# Radio_XBP9X_DMRS_001.net
KiCad netlist of a schematic drawn in Altium Designer
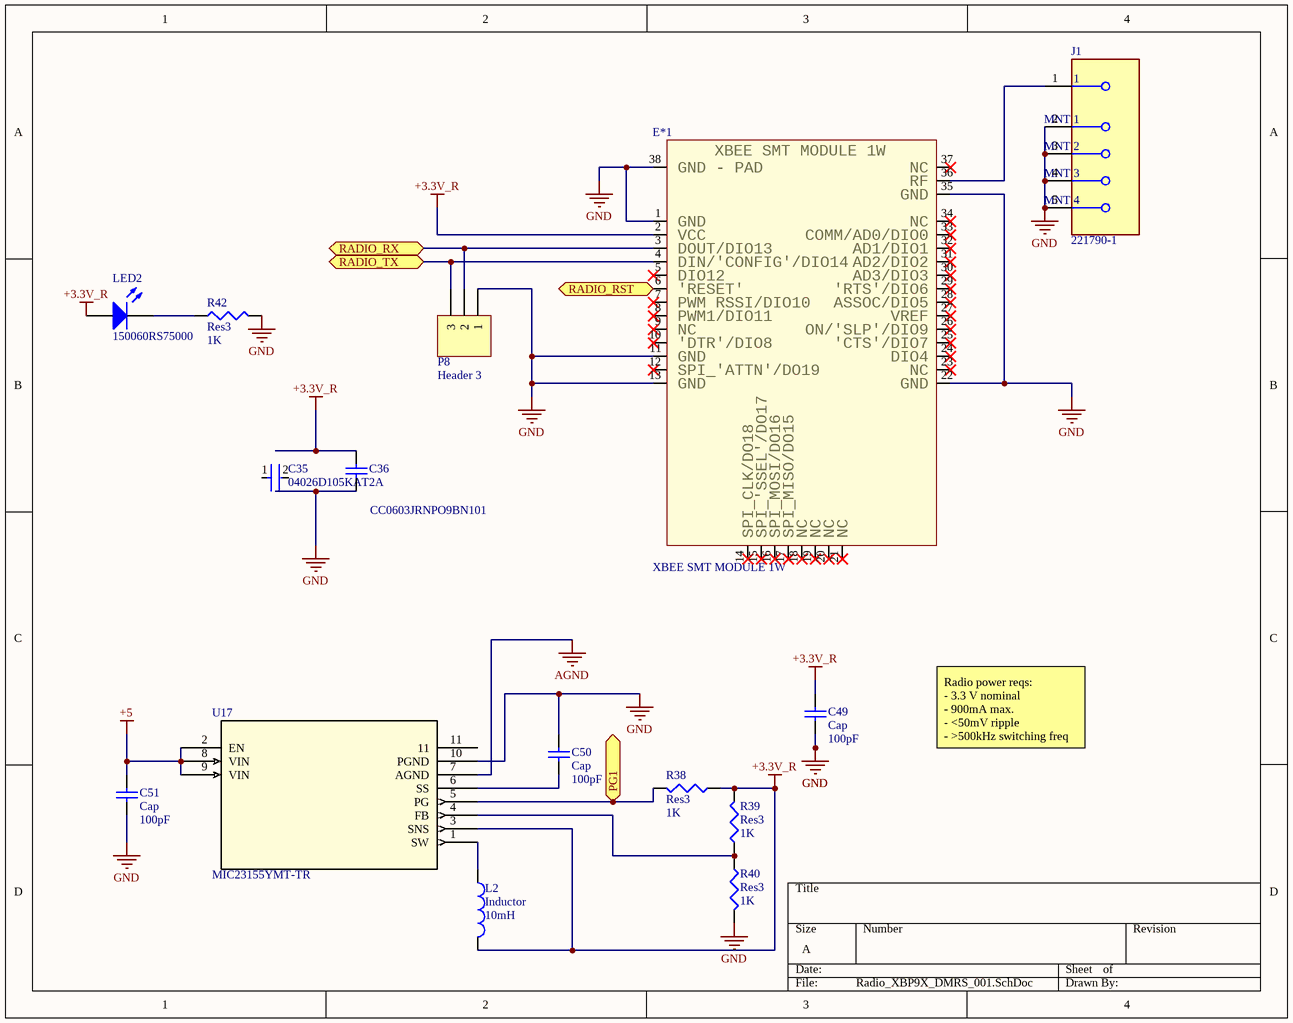
[diagram p0: Radio_XBP9X_DMRS_001.SchDoc]

(export (version "E")
  (design (tool "Eeschema 10.0.6"))
  (components
    (comp (ref "C35")
      (value "04026D105KAT2A")
      (footprint "FP-0402-L_1_0_1-W_0_5_0_1-MFG")
      (description "General Purpose Ceramic Capacitor, 0402, 1uF, 10%, X5R, 15%, 6.3V")
      (fields (field (name "TOLERANCE") "10%") (field (name "VOLTAGE") "6.3V"))
      (libsource (lib "Altium Content Vault") (part "b4654b650e69147ec39a6b967a45e02"))
    )
    (comp (ref "C36")
      (value "CC0603JRNPO9BN101")
      (footprint "CAPC1608X90X40ML10T20")
      (description "Chip Capacitor, 100 pF, +/- 5%, 50 V, -55 to 125 degC, 0603 (1608 Metric), RoHS, Tape and Reel")
      (fields (field (name "TOLERANCE") "5%") (field (name "VOLTAGE") "50V"))
      (libsource (lib "Altium Content Vault") (part "CAP-NP-2"))
    )
    (comp (ref "C49")
      (value "Cap")
      (footprint "RAD-0.3")
      (description "Capacitor")
      (fields (field (name "ALTIUM_VALUE") "100pF") (field (name "PUBLISHER") "Altium Limited"))
      (libsource (lib "Miscellaneous Devices") (part "Cap"))
    )
    (comp (ref "C50")
      (value "Cap")
      (footprint "RAD-0.3")
      (description "Capacitor")
      (fields (field (name "ALTIUM_VALUE") "100pF") (field (name "PUBLISHER") "Altium Limited"))
      (libsource (lib "Miscellaneous Devices") (part "Cap"))
    )
    (comp (ref "C51")
      (value "Cap")
      (footprint "RAD-0.3")
      (description "Capacitor")
      (fields (field (name "ALTIUM_VALUE") "100pF") (field (name "PUBLISHER") "Altium Limited"))
      (libsource (lib "Miscellaneous Devices") (part "Cap"))
    )
    (comp (ref "E*1")
      (value "XBEE SMT MODULE 1W")
      (libsource (lib "Xbee3_1W_Customer_Sch_Symbol") (part "XBEE SMT MODULE 1W"))
    )
    (comp (ref "J1")
      (value "221790-1")
      (footprint "FP-221790-1-MFG")
      (description "CONN SMA JACK R/A 50 OHM PCB")
      (fields
        (field (name "OCTOPART") "https://octopart.com/2217901-te+connectivity+%2F+amp-3339836")
        (field (name "MANUFACTURER") "TE Connectivity / AMP")
      )
      (libsource (lib "Altium Content Vault") (part "c65b8a639cdaef1819ea20b5466f8fa"))
    )
    (comp (ref "L2")
      (value "Inductor")
      (footprint "0402-A")
      (fields (field (name "ALTIUM_VALUE") "10mH") (field (name "PUBLISHER") "Altium Limited"))
      (libsource (lib "Miscellaneous Devices") (part "Inductor"))
    )
    (comp (ref "LED2")
      (value "150060RS75000")
      (footprint "0603_A")
      (description "SMD mono-color Chip LED, WL-SMCW, Red")
      (fields (field (name "MANUFACTURER") "Wuerth Elektronik"))
      (libsource (lib "Altium Content Vault") (part "WE-LED_K1A2-2"))
    )
    (comp (ref "P8")
      (value "Header 3")
      (footprint "HDR1X3")
      (description "Header, 3-Pin")
      (fields (field (name "PUBLISHER") "Altium Limited"))
      (libsource (lib "Miscellaneous Connectors") (part "Header 3"))
    )
    (comp (ref "R38")
      (value "Res3")
      (footprint "J1-0603")
      (description "Resistor")
      (fields (field (name "ALTIUM_VALUE") "1K") (field (name "PUBLISHER") "Altium Limited"))
      (libsource (lib "Miscellaneous Devices") (part "Res3"))
    )
    (comp (ref "R39")
      (value "Res3")
      (footprint "J1-0603")
      (description "Resistor")
      (fields (field (name "ALTIUM_VALUE") "1K") (field (name "PUBLISHER") "Altium Limited"))
      (libsource (lib "Miscellaneous Devices") (part "Res3"))
    )
    (comp (ref "R40")
      (value "Res3")
      (footprint "J1-0603")
      (description "Resistor")
      (fields (field (name "ALTIUM_VALUE") "1K") (field (name "PUBLISHER") "Altium Limited"))
      (libsource (lib "Miscellaneous Devices") (part "Res3"))
    )
    (comp (ref "R42")
      (value "Res3")
      (footprint "J1-0603")
      (description "Resistor")
      (fields (field (name "ALTIUM_VALUE") "1K") (field (name "PUBLISHER") "Altium Limited"))
      (libsource (lib "Miscellaneous Devices") (part "Res3"))
    )
    (comp (ref "U17")
      (value "MIC23155YMT-TR")
      (footprint "DFN-10_MCH")
      (description "No Description Available")
      (fields (field (name "COPYRIGHT") "Copyright (C) 2018 Accelerated Designs. All rights reserved"))
      (libsource (lib "MIC23155") (part "MIC23155YMT-TR"))
    )
  )
  (nets
    (net (code "1") (name "+3.3V_R") (class "Default")
      (node (ref "C36") (pin "2") (pinfunction "2_2") (pintype "passive"))
      (node (ref "C49") (pin "2") (pinfunction "2_2") (pintype "passive"))
      (node (ref "E*1") (pin "2") (pintype "passive"))
      (node (ref "L2") (pin "2") (pinfunction "2_2") (pintype "passive"))
      (node (ref "LED2") (pin "2") (pinfunction "A_2") (pintype "passive"))
      (node (ref "R38") (pin "1") (pinfunction "1_1") (pintype "passive"))
      (node (ref "R39") (pin "2") (pinfunction "2_2") (pintype "passive"))
      (node (ref "U17") (pin "3") (pinfunction "SNS_3") (pintype "output"))
    )
    (net (code "2") (name "+5") (class "Default")
      (node (ref "C51") (pin "2") (pinfunction "2_2") (pintype "passive"))
      (node (ref "U17") (pin "2") (pinfunction "EN_2") (pintype "passive"))
      (node (ref "U17") (pin "8") (pinfunction "VIN_8") (pintype "input"))
      (node (ref "U17") (pin "9") (pinfunction "VIN_9") (pintype "input"))
    )
    (net (code "3") (name "/PG1") (class "Default")
      (node (ref "R38") (pin "2") (pinfunction "2_2") (pintype "passive"))
      (node (ref "U17") (pin "5") (pinfunction "PG_5") (pintype "output"))
    )
    (net (code "4") (name "/RADIO_RST") (class "Default") (node (ref "E*1") (pin "6") (pintype "passive")))
    (net (code "5") (name "/RADIO_RX") (class "Default")
      (node (ref "E*1") (pin "3") (pintype "passive"))
      (node (ref "P8") (pin "2") (pinfunction "2_2") (pintype "passive"))
    )
    (net (code "6") (name "/RADIO_TX") (class "Default")
      (node (ref "E*1") (pin "4") (pintype "passive"))
      (node (ref "P8") (pin "3") (pinfunction "3_3") (pintype "passive"))
    )
    (net (code "7") (name "AGND") (class "Default")
      (node (ref "U17") (pin "7") (pinfunction "AGND_7") (pintype "power_in"))
    )
    (net (code "8") (name "GND") (class "Default")
      (node (ref "C36") (pin "1") (pinfunction "1_1") (pintype "passive"))
      (node (ref "C49") (pin "1") (pinfunction "1_1") (pintype "passive"))
      (node (ref "C50") (pin "2") (pinfunction "2_2") (pintype "passive"))
      (node (ref "C51") (pin "1") (pinfunction "1_1") (pintype "passive"))
      (node (ref "E*1") (pin "1") (pintype "passive"))
      (node (ref "E*1") (pin "11") (pintype "passive"))
      (node (ref "E*1") (pin "13") (pintype "passive"))
      (node (ref "E*1") (pin "22") (pintype "passive"))
      (node (ref "E*1") (pin "35") (pintype "passive"))
      (node (ref "E*1") (pin "38") (pintype "passive"))
      (node (ref "J1") (pin "2") (pinfunction "MNT_1_2") (pintype "passive"))
      (node (ref "J1") (pin "3") (pinfunction "MNT_2_3") (pintype "passive"))
      (node (ref "J1") (pin "4") (pinfunction "MNT_3_4") (pintype "passive"))
      (node (ref "J1") (pin "5") (pinfunction "MNT_4_5") (pintype "passive"))
      (node (ref "P8") (pin "1") (pinfunction "1_1") (pintype "passive"))
      (node (ref "R40") (pin "2") (pinfunction "2_2") (pintype "passive"))
      (node (ref "R42") (pin "2") (pinfunction "2_2") (pintype "passive"))
      (node (ref "U17") (pin "10") (pinfunction "PGND_10") (pintype "power_in"))
    )
    (net (code "9") (name "Net-(E*1-Pad36)") (class "Default")
      (node (ref "E*1") (pin "36") (pintype "passive"))
      (node (ref "J1") (pin "1") (pinfunction "1_1") (pintype "passive"))
    )
    (net (code "10") (name "Net-(LED2-K)") (class "Default")
      (node (ref "LED2") (pin "1") (pinfunction "K_1") (pintype "passive"))
      (node (ref "R42") (pin "1") (pinfunction "1_1") (pintype "passive"))
    )
    (net (code "11") (name "Net-(U17-FB)") (class "Default")
      (node (ref "R39") (pin "1") (pinfunction "1_1") (pintype "passive"))
      (node (ref "R40") (pin "1") (pinfunction "1_1") (pintype "passive"))
      (node (ref "U17") (pin "4") (pinfunction "FB_4") (pintype "output"))
    )
    (net (code "12") (name "Net-(U17-SS)") (class "Default")
      (node (ref "C50") (pin "1") (pinfunction "1_1") (pintype "passive"))
      (node (ref "U17") (pin "6") (pinfunction "SS_6") (pintype "passive"))
    )
    (net (code "13") (name "Net-(U17-SW)") (class "Default")
      (node (ref "L2") (pin "1") (pinfunction "1_1") (pintype "passive"))
      (node (ref "U17") (pin "1") (pinfunction "SW_1") (pintype "output"))
    )
    (net (code "14") (name "unconnected-(C35-Pad1)") (class "Default")
      (node (ref "C35") (pin "1") (pinfunction "1_1") (pintype "passive"))
    )
    (net (code "15") (name "unconnected-(C35-Pad2)") (class "Default")
      (node (ref "C35") (pin "2") (pinfunction "2_2") (pintype "passive"))
    )
    (net (code "16") (name "unconnected-(E*1-Pad5)") (class "Default")
      (node (ref "E*1") (pin "5") (pintype "passive+no_connect"))
    )
    (net (code "17") (name "unconnected-(E*1-Pad7)") (class "Default")
      (node (ref "E*1") (pin "7") (pintype "passive+no_connect"))
    )
    (net (code "18") (name "unconnected-(E*1-Pad8)") (class "Default")
      (node (ref "E*1") (pin "8") (pintype "passive+no_connect"))
    )
    (net (code "19") (name "unconnected-(E*1-Pad9)") (class "Default")
      (node (ref "E*1") (pin "9") (pintype "passive+no_connect"))
    )
    (net (code "20") (name "unconnected-(E*1-Pad10)") (class "Default")
      (node (ref "E*1") (pin "10") (pintype "passive+no_connect"))
    )
    (net (code "21") (name "unconnected-(E*1-Pad12)") (class "Default")
      (node (ref "E*1") (pin "12") (pintype "passive+no_connect"))
    )
    (net (code "22") (name "unconnected-(E*1-Pad14)") (class "Default")
      (node (ref "E*1") (pin "14") (pintype "passive+no_connect"))
    )
    (net (code "23") (name "unconnected-(E*1-Pad15)") (class "Default")
      (node (ref "E*1") (pin "15") (pintype "passive+no_connect"))
    )
    (net (code "24") (name "unconnected-(E*1-Pad16)") (class "Default")
      (node (ref "E*1") (pin "16") (pintype "passive+no_connect"))
    )
    (net (code "25") (name "unconnected-(E*1-Pad17)") (class "Default")
      (node (ref "E*1") (pin "17") (pintype "passive+no_connect"))
    )
    (net (code "26") (name "unconnected-(E*1-Pad18)") (class "Default")
      (node (ref "E*1") (pin "18") (pintype "passive+no_connect"))
    )
    (net (code "27") (name "unconnected-(E*1-Pad19)") (class "Default")
      (node (ref "E*1") (pin "19") (pintype "passive+no_connect"))
    )
    (net (code "28") (name "unconnected-(E*1-Pad20)") (class "Default")
      (node (ref "E*1") (pin "20") (pintype "passive+no_connect"))
    )
    (net (code "29") (name "unconnected-(E*1-Pad21)") (class "Default")
      (node (ref "E*1") (pin "21") (pintype "passive+no_connect"))
    )
    (net (code "30") (name "unconnected-(E*1-Pad23)") (class "Default")
      (node (ref "E*1") (pin "23") (pintype "passive+no_connect"))
    )
    (net (code "31") (name "unconnected-(E*1-Pad24)") (class "Default")
      (node (ref "E*1") (pin "24") (pintype "passive+no_connect"))
    )
    (net (code "32") (name "unconnected-(E*1-Pad25)") (class "Default")
      (node (ref "E*1") (pin "25") (pintype "passive+no_connect"))
    )
    (net (code "33") (name "unconnected-(E*1-Pad26)") (class "Default")
      (node (ref "E*1") (pin "26") (pintype "passive+no_connect"))
    )
    (net (code "34") (name "unconnected-(E*1-Pad27)") (class "Default")
      (node (ref "E*1") (pin "27") (pintype "passive+no_connect"))
    )
    (net (code "35") (name "unconnected-(E*1-Pad28)") (class "Default")
      (node (ref "E*1") (pin "28") (pintype "passive+no_connect"))
    )
    (net (code "36") (name "unconnected-(E*1-Pad29)") (class "Default")
      (node (ref "E*1") (pin "29") (pintype "passive+no_connect"))
    )
    (net (code "37") (name "unconnected-(E*1-Pad30)") (class "Default")
      (node (ref "E*1") (pin "30") (pintype "passive+no_connect"))
    )
    (net (code "38") (name "unconnected-(E*1-Pad31)") (class "Default")
      (node (ref "E*1") (pin "31") (pintype "passive+no_connect"))
    )
    (net (code "39") (name "unconnected-(E*1-Pad32)") (class "Default")
      (node (ref "E*1") (pin "32") (pintype "passive+no_connect"))
    )
    (net (code "40") (name "unconnected-(E*1-Pad33)") (class "Default")
      (node (ref "E*1") (pin "33") (pintype "passive+no_connect"))
    )
    (net (code "41") (name "unconnected-(E*1-Pad34)") (class "Default")
      (node (ref "E*1") (pin "34") (pintype "passive+no_connect"))
    )
    (net (code "42") (name "unconnected-(E*1-Pad37)") (class "Default")
      (node (ref "E*1") (pin "37") (pintype "passive+no_connect"))
    )
    (net (code "43") (name "unconnected-(U17-Pad11)") (class "Default")
      (node (ref "U17") (pin "11") (pinfunction "11_11") (pintype "passive"))
    )
  )
)
